# home_auto.net
KiCad netlist of a schematic drawn in EasyEDA
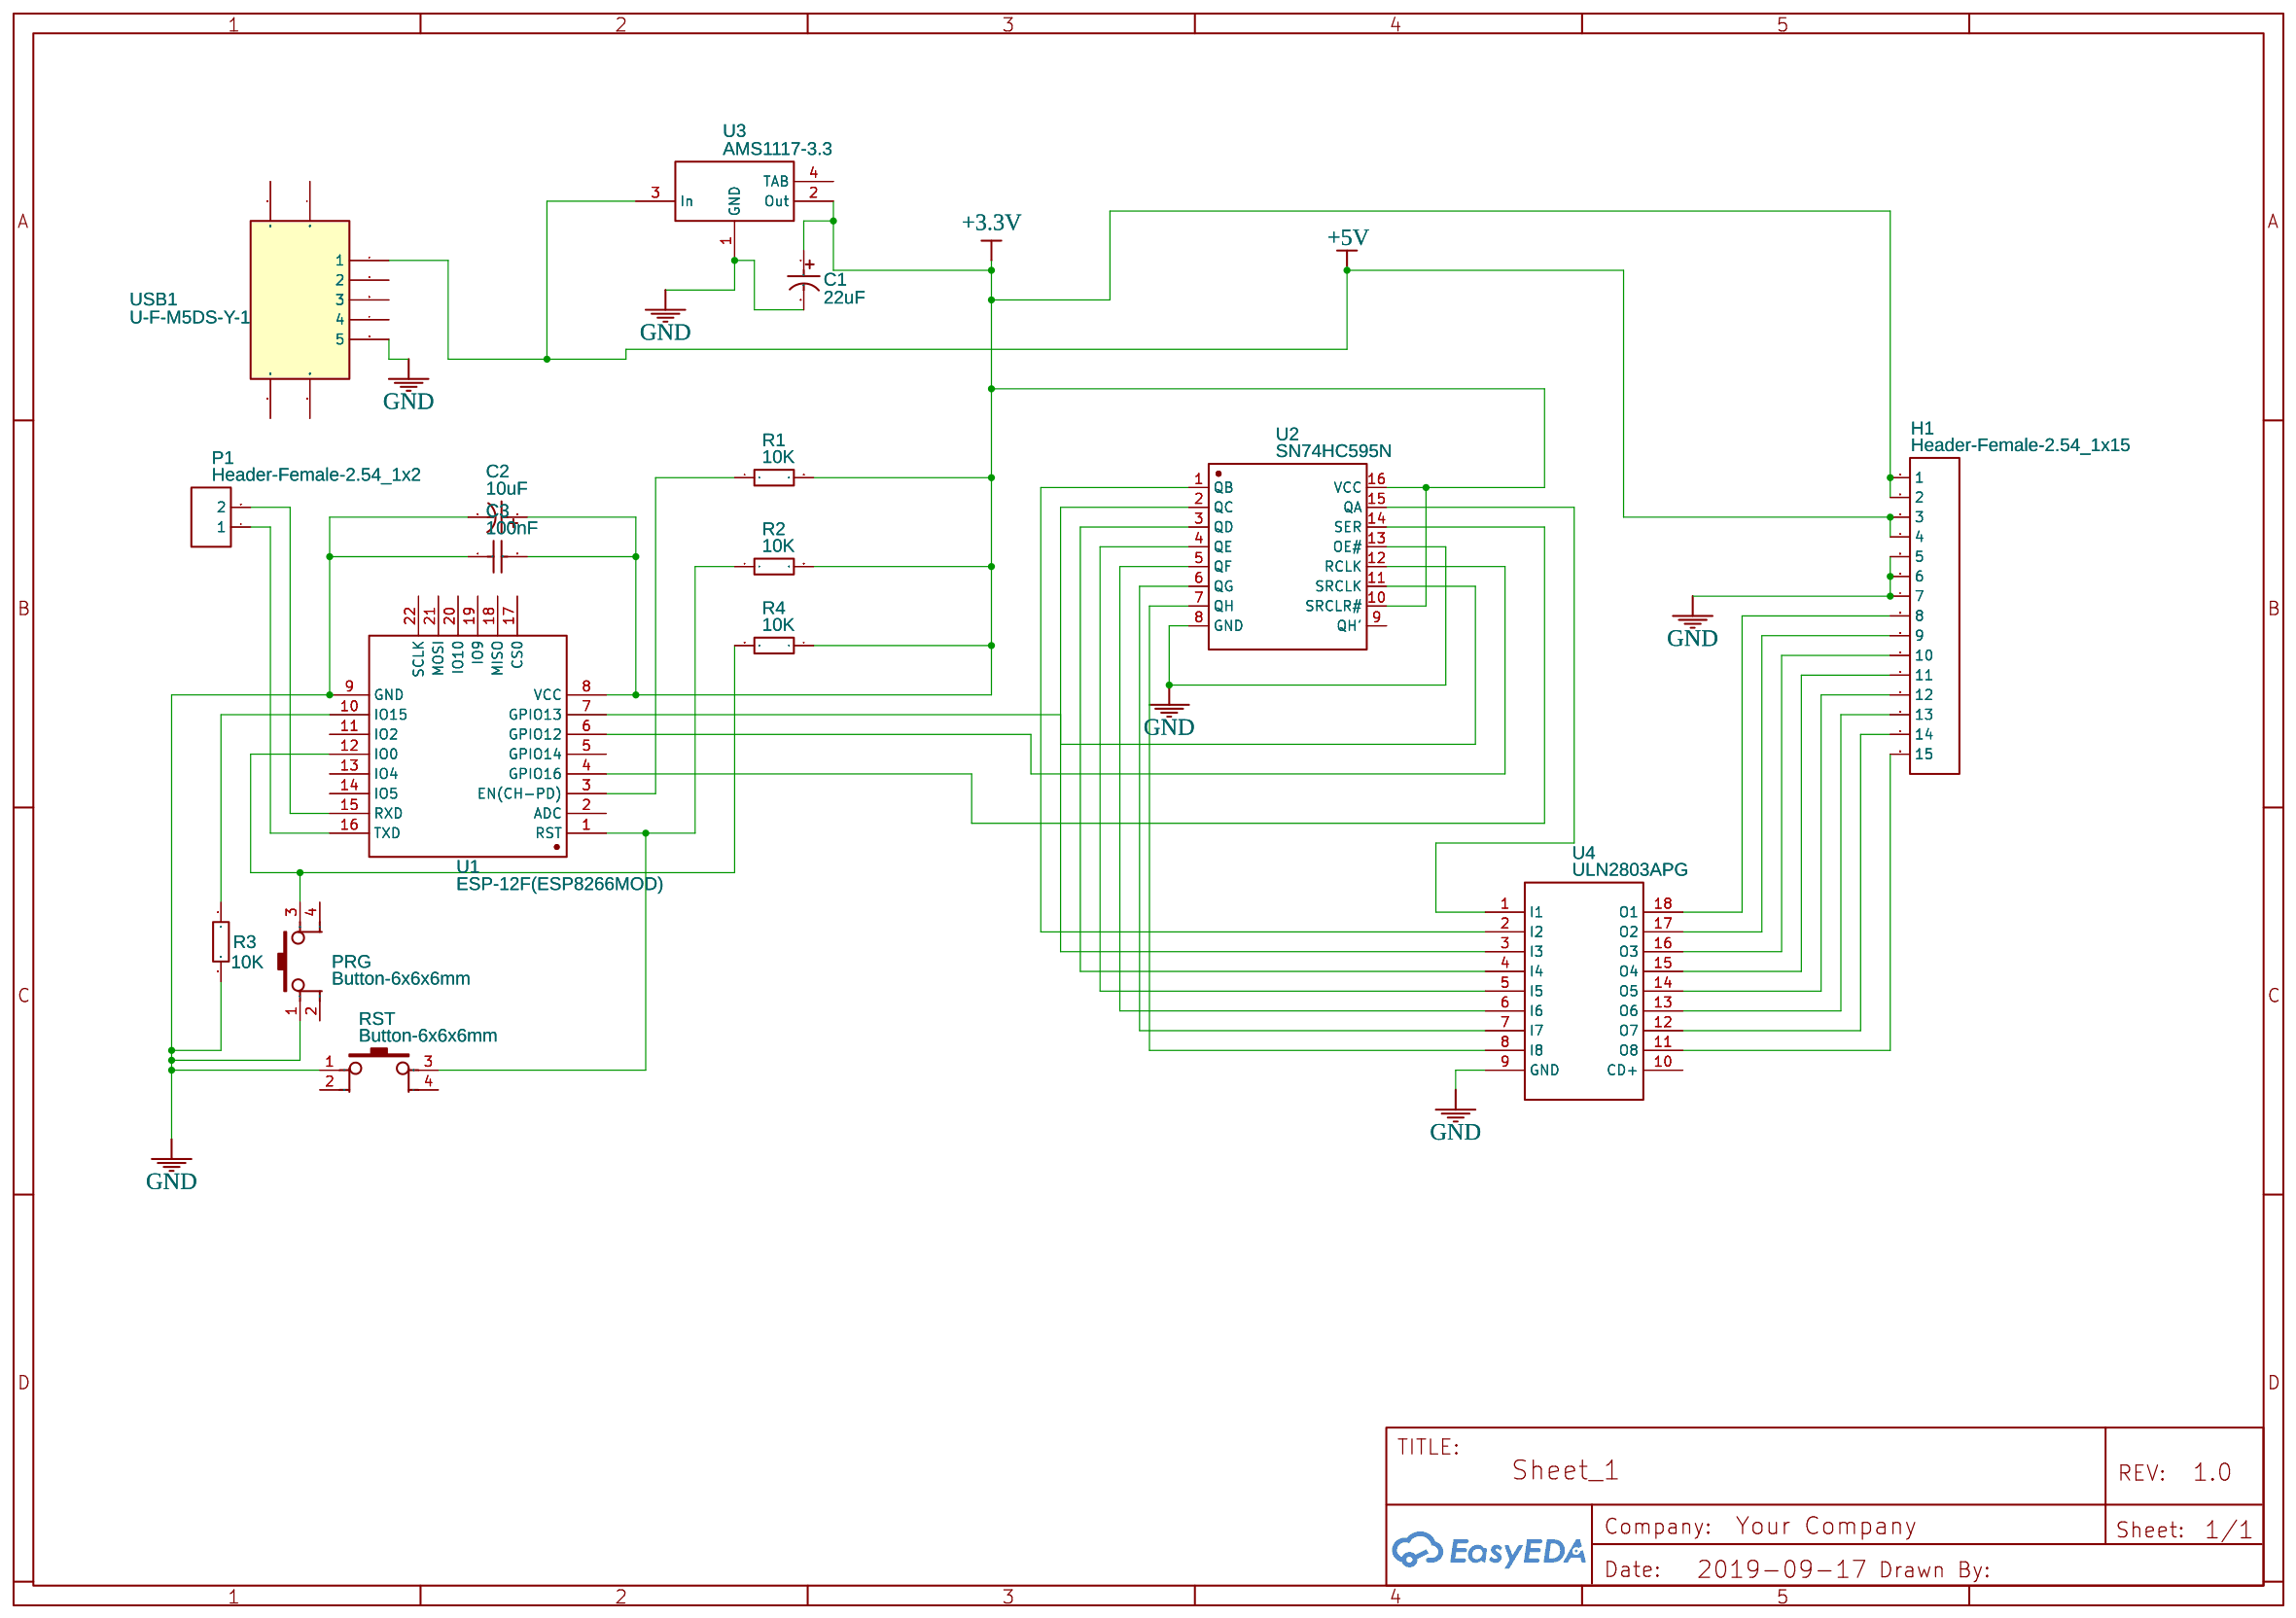
[diagram p0: schematic sheet]

(export (version "E")
  (design (tool "Eeschema 10.0.6"))
  (components
    (comp (ref "C1")
      (value "22uF")
      (fields
        (field (name "BOM_Manufacturer Part") "22uF 16V 5*11")
        (field (name "BOM_Supplier Part") "C43844")
      )
      (libsource (lib "") (part "22uF 16V 5*11"))
    )
    (comp (ref "C2")
      (value "10uF")
      (fields
        (field (name "BOM_Manufacturer Part") "10uF 16V 5*11")
        (field (name "BOM_Supplier Part") "C43799")
      )
      (libsource (lib "") (part "10uF 16V 5*11"))
    )
    (comp (ref "C3")
      (value "100nF")
      (fields
        (field (name "BOM_Manufacturer Part") "MPP104J4130510LC")
        (field (name "BOM_Supplier Part") "C109501")
      )
      (libsource (lib "") (part "MPP104J4130510LC"))
    )
    (comp (ref "H1")
      (value "Header-Female-2.54_1x15")
      (fields
        (field (name "BOM_Manufacturer Part") "220S-1*15P H=8.5MM Ytype Gold-plated")
        (field (name "BOM_Supplier Part") "C124408")
      )
      (libsource (lib "") (part "Unknown_970_310"))
    )
    (comp (ref "P1")
      (value "Header-Female-2.54_1x2")
      (fields
        (field (name "BOM_Manufacturer Part") "2.54-1*2PFemale")
        (field (name "BOM_Supplier Part") "C49661")
      )
      (libsource (lib "") (part "Unknown_105_255"))
    )
    (comp (ref "PRG")
      (value "Button-6x6x6mm")
      (fields
        (field (name "BOM_Manufacturer Part") "Switch,6*6*6Plastic head,260G, 0.25mm,Straight line")
        (field (name "BOM_Supplier Part") "C71836")
      )
      (libsource (lib "") (part "Unknown_145_480"))
    )
    (comp (ref "R1")
      (value "10K")
      (fields
        (field (name "BOM_Manufacturer Part") "MOR01SJ0103A10")
        (field (name "BOM_Supplier Part") "C64666")
      )
      (libsource (lib "") (part "MOR01SJ0103A10_1"))
    )
    (comp (ref "R2")
      (value "10K")
      (fields
        (field (name "BOM_Manufacturer Part") "MOR01SJ0103A10")
        (field (name "BOM_Supplier Part") "C64666")
      )
      (libsource (lib "") (part "MOR01SJ0103A10_1"))
    )
    (comp (ref "R3")
      (value "10K")
      (fields
        (field (name "BOM_Manufacturer Part") "MOR01SJ0103A10")
        (field (name "BOM_Supplier Part") "C64666")
      )
      (libsource (lib "") (part "MOR01SJ0103A10_2"))
    )
    (comp (ref "R4")
      (value "10K")
      (fields
        (field (name "BOM_Manufacturer Part") "MOR01SJ0103A10")
        (field (name "BOM_Supplier Part") "C64666")
      )
      (libsource (lib "") (part "MOR01SJ0103A10"))
    )
    (comp (ref "RST")
      (value "Button-6x6x6mm")
      (fields
        (field (name "BOM_Manufacturer Part") "Switch,6*6*6Plastic head,260G, 0.25mm,Straight line")
        (field (name "BOM_Supplier Part") "C71836")
      )
      (libsource (lib "") (part "Unknown_185_535"))
    )
    (comp (ref "U1")
      (value "ESP-12F(ESP8266MOD)")
      (fields (field (name "BOM_Supplier Part") "C82891"))
      (libsource (lib "") (part "Unknown_230_365"))
    )
    (comp (ref "U2")
      (value "SN74HC595N")
      (fields (field (name "BOM_Supplier Part") "C78711"))
      (libsource (lib "") (part "Unknown_645_275"))
    )
    (comp (ref "U3")
      (value "AMS1117-3.3")
      (fields (field (name "BOM_Supplier Part") "C6186"))
      (libsource (lib "") (part "Unknown_365_100"))
    )
    (comp (ref "U4")
      (value "ULN2803APG")
      (fields (field (name "BOM_Supplier Part") "C5252"))
      (libsource (lib "") (part "Unknown_795_495"))
    )
    (comp (ref "USB1")
      (value "U-F-M5DS-Y-1")
      (fields (field (name "BOM_Supplier Part") "C106818"))
      (libsource (lib "") (part "Unknown_155_145"))
    )
  )
  (nets
    (net (code "1") (name "+3.3V") (class "Default")
      (node (ref "C1") (pin "1") (pinfunction "1_1") (pintype "input"))
      (node (ref "C2") (pin "1") (pinfunction "1_1") (pintype "input"))
      (node (ref "C3") (pin "2") (pinfunction "2_2") (pintype "input"))
      (node (ref "H1") (pin "1") (pinfunction "1_1") (pintype "unspecified"))
      (node (ref "H1") (pin "2") (pinfunction "2_2") (pintype "unspecified"))
      (node (ref "R1") (pin "2") (pinfunction "2_2") (pintype "unspecified"))
      (node (ref "R2") (pin "2") (pinfunction "2_2") (pintype "unspecified"))
      (node (ref "R4") (pin "1") (pinfunction "1_1") (pintype "unspecified"))
      (node (ref "U1") (pin "8") (pinfunction "VCC_8") (pintype "unspecified"))
      (node (ref "U2") (pin "10") (pinfunction "SRCLR#_10") (pintype "unspecified"))
      (node (ref "U2") (pin "16") (pinfunction "VCC_16") (pintype "unspecified"))
      (node (ref "U3") (pin "2") (pinfunction "Out_2") (pintype "unspecified"))
    )
    (net (code "2") (name "+5V") (class "Default")
      (node (ref "H1") (pin "3") (pinfunction "3_3") (pintype "unspecified"))
      (node (ref "H1") (pin "4") (pinfunction "4_4") (pintype "unspecified"))
      (node (ref "U3") (pin "3") (pinfunction "In_3") (pintype "unspecified"))
      (node (ref "USB1") (pin "1") (pinfunction "1_1") (pintype "input"))
    )
    (net (code "3") (name "GND") (class "Default")
      (node (ref "C1") (pin "2") (pinfunction "2_2") (pintype "input"))
      (node (ref "C2") (pin "2") (pinfunction "2_2") (pintype "input"))
      (node (ref "C3") (pin "1") (pinfunction "1_1") (pintype "input"))
      (node (ref "H1") (pin "5") (pinfunction "5_5") (pintype "unspecified"))
      (node (ref "H1") (pin "6") (pinfunction "6_6") (pintype "unspecified"))
      (node (ref "H1") (pin "7") (pinfunction "7_7") (pintype "unspecified"))
      (node (ref "PRG") (pin "1") (pinfunction "1_1") (pintype "input"))
      (node (ref "R3") (pin "2") (pinfunction "2_2") (pintype "unspecified"))
      (node (ref "RST") (pin "1") (pinfunction "1_1") (pintype "input"))
      (node (ref "U1") (pin "9") (pinfunction "GND_9") (pintype "unspecified"))
      (node (ref "U2") (pin "13") (pinfunction "OE#_13") (pintype "unspecified"))
      (node (ref "U2") (pin "8") (pinfunction "GND_8") (pintype "unspecified"))
      (node (ref "U3") (pin "1") (pinfunction "GND_1") (pintype "unspecified"))
      (node (ref "U4") (pin "9") (pinfunction "GND_9") (pintype "passive"))
      (node (ref "USB1") (pin "5") (pinfunction "5_5") (pintype "input"))
    )
    (net (code "4") (name "Net-(U1-EN(CH-PD))") (class "Default")
      (node (ref "R1") (pin "1") (pinfunction "1_1") (pintype "unspecified"))
      (node (ref "U1") (pin "3") (pinfunction "EN(CH-PD)_3") (pintype "unspecified"))
    )
    (net (code "5") (name "Net-(U1-GPIO12)") (class "Default")
      (node (ref "U1") (pin "6") (pinfunction "GPIO12_6") (pintype "unspecified"))
      (node (ref "U2") (pin "12") (pinfunction "RCLK_12") (pintype "unspecified"))
    )
    (net (code "6") (name "Net-(U1-GPIO13)") (class "Default")
      (node (ref "U1") (pin "7") (pinfunction "GPIO13_7") (pintype "unspecified"))
      (node (ref "U2") (pin "11") (pinfunction "SRCLK_11") (pintype "unspecified"))
    )
    (net (code "7") (name "Net-(U1-GPIO16)") (class "Default")
      (node (ref "U1") (pin "4") (pinfunction "GPIO16_4") (pintype "unspecified"))
      (node (ref "U2") (pin "14") (pinfunction "SER_14") (pintype "unspecified"))
    )
    (net (code "8") (name "Net-(U1-IO0)") (class "Default")
      (node (ref "PRG") (pin "3") (pinfunction "3_3") (pintype "input"))
      (node (ref "R4") (pin "2") (pinfunction "2_2") (pintype "unspecified"))
      (node (ref "U1") (pin "12") (pinfunction "IO0_12") (pintype "unspecified"))
    )
    (net (code "9") (name "Net-(U1-IO15)") (class "Default")
      (node (ref "R3") (pin "1") (pinfunction "1_1") (pintype "unspecified"))
      (node (ref "U1") (pin "10") (pinfunction "IO15_10") (pintype "unspecified"))
    )
    (net (code "10") (name "Net-(U1-RST)") (class "Default")
      (node (ref "R2") (pin "1") (pinfunction "1_1") (pintype "unspecified"))
      (node (ref "RST") (pin "3") (pinfunction "3_3") (pintype "input"))
      (node (ref "U1") (pin "1") (pinfunction "RST_1") (pintype "unspecified"))
    )
    (net (code "11") (name "Net-(U1-RXD)") (class "Default")
      (node (ref "P1") (pin "2") (pinfunction "2_2") (pintype "input"))
      (node (ref "U1") (pin "15") (pinfunction "RXD_15") (pintype "unspecified"))
    )
    (net (code "12") (name "Net-(U1-TXD)") (class "Default")
      (node (ref "P1") (pin "1") (pinfunction "1_1") (pintype "input"))
      (node (ref "U1") (pin "16") (pinfunction "TXD_16") (pintype "unspecified"))
    )
    (net (code "13") (name "Net-(U2-QA)") (class "Default")
      (node (ref "U2") (pin "15") (pinfunction "QA_15") (pintype "unspecified"))
      (node (ref "U4") (pin "1") (pinfunction "I1_1") (pintype "input"))
    )
    (net (code "14") (name "Net-(U2-QB)") (class "Default")
      (node (ref "U2") (pin "1") (pinfunction "QB_1") (pintype "unspecified"))
      (node (ref "U4") (pin "2") (pinfunction "I2_2") (pintype "input"))
    )
    (net (code "15") (name "Net-(U2-QC)") (class "Default")
      (node (ref "U2") (pin "2") (pinfunction "QC_2") (pintype "unspecified"))
      (node (ref "U4") (pin "3") (pinfunction "I3_3") (pintype "input"))
    )
    (net (code "16") (name "Net-(U2-QD)") (class "Default")
      (node (ref "U2") (pin "3") (pinfunction "QD_3") (pintype "unspecified"))
      (node (ref "U4") (pin "4") (pinfunction "I4_4") (pintype "input"))
    )
    (net (code "17") (name "Net-(U2-QE)") (class "Default")
      (node (ref "U2") (pin "4") (pinfunction "QE_4") (pintype "unspecified"))
      (node (ref "U4") (pin "5") (pinfunction "I5_5") (pintype "input"))
    )
    (net (code "18") (name "Net-(U2-QF)") (class "Default")
      (node (ref "U2") (pin "5") (pinfunction "QF_5") (pintype "unspecified"))
      (node (ref "U4") (pin "6") (pinfunction "I6_6") (pintype "input"))
    )
    (net (code "19") (name "Net-(U2-QG)") (class "Default")
      (node (ref "U2") (pin "6") (pinfunction "QG_6") (pintype "unspecified"))
      (node (ref "U4") (pin "7") (pinfunction "I7_7") (pintype "input"))
    )
    (net (code "20") (name "Net-(U2-QH)") (class "Default")
      (node (ref "U2") (pin "7") (pinfunction "QH_7") (pintype "unspecified"))
      (node (ref "U4") (pin "8") (pinfunction "I8_8") (pintype "input"))
    )
    (net (code "21") (name "Net-(U4-O1)") (class "Default")
      (node (ref "H1") (pin "8") (pinfunction "8_8") (pintype "unspecified"))
      (node (ref "U4") (pin "18") (pinfunction "O1_18") (pintype "unspecified"))
    )
    (net (code "22") (name "Net-(U4-O2)") (class "Default")
      (node (ref "H1") (pin "9") (pinfunction "9_9") (pintype "unspecified"))
      (node (ref "U4") (pin "17") (pinfunction "O2_17") (pintype "unspecified"))
    )
    (net (code "23") (name "Net-(U4-O3)") (class "Default")
      (node (ref "H1") (pin "10") (pinfunction "10_10") (pintype "unspecified"))
      (node (ref "U4") (pin "16") (pinfunction "O3_16") (pintype "unspecified"))
    )
    (net (code "24") (name "Net-(U4-O4)") (class "Default")
      (node (ref "H1") (pin "11") (pinfunction "11_11") (pintype "unspecified"))
      (node (ref "U4") (pin "15") (pinfunction "O4_15") (pintype "unspecified"))
    )
    (net (code "25") (name "Net-(U4-O5)") (class "Default")
      (node (ref "H1") (pin "12") (pinfunction "12_12") (pintype "unspecified"))
      (node (ref "U4") (pin "14") (pinfunction "O5_14") (pintype "unspecified"))
    )
    (net (code "26") (name "Net-(U4-O6)") (class "Default")
      (node (ref "H1") (pin "13") (pinfunction "13_13") (pintype "unspecified"))
      (node (ref "U4") (pin "13") (pinfunction "O6_13") (pintype "unspecified"))
    )
    (net (code "27") (name "Net-(U4-O7)") (class "Default")
      (node (ref "H1") (pin "14") (pinfunction "14_14") (pintype "unspecified"))
      (node (ref "U4") (pin "12") (pinfunction "O7_12") (pintype "unspecified"))
    )
    (net (code "28") (name "Net-(U4-O8)") (class "Default")
      (node (ref "H1") (pin "15") (pinfunction "15_15") (pintype "unspecified"))
      (node (ref "U4") (pin "11") (pinfunction "O8_11") (pintype "unspecified"))
    )
    (net (code "29") (name "unconnected-(PRG-Pad2)") (class "Default")
      (node (ref "PRG") (pin "2") (pinfunction "2_2") (pintype "input"))
    )
    (net (code "30") (name "unconnected-(PRG-Pad4)") (class "Default")
      (node (ref "PRG") (pin "4") (pinfunction "4_4") (pintype "input"))
    )
    (net (code "31") (name "unconnected-(RST-Pad2)") (class "Default")
      (node (ref "RST") (pin "2") (pinfunction "2_2") (pintype "input"))
    )
    (net (code "32") (name "unconnected-(RST-Pad4)") (class "Default")
      (node (ref "RST") (pin "4") (pinfunction "4_4") (pintype "input"))
    )
    (net (code "33") (name "unconnected-(U1-ADC-Pad2)") (class "Default")
      (node (ref "U1") (pin "2") (pinfunction "ADC_2") (pintype "unspecified"))
    )
    (net (code "34") (name "unconnected-(U1-CS0-Pad17)") (class "Default")
      (node (ref "U1") (pin "17") (pinfunction "CS0_17") (pintype "unspecified"))
    )
    (net (code "35") (name "unconnected-(U1-GPIO14-Pad5)") (class "Default")
      (node (ref "U1") (pin "5") (pinfunction "GPIO14_5") (pintype "unspecified"))
    )
    (net (code "36") (name "unconnected-(U1-IO2-Pad11)") (class "Default")
      (node (ref "U1") (pin "11") (pinfunction "IO2_11") (pintype "unspecified"))
    )
    (net (code "37") (name "unconnected-(U1-IO4-Pad13)") (class "Default")
      (node (ref "U1") (pin "13") (pinfunction "IO4_13") (pintype "unspecified"))
    )
    (net (code "38") (name "unconnected-(U1-IO5-Pad14)") (class "Default")
      (node (ref "U1") (pin "14") (pinfunction "IO5_14") (pintype "unspecified"))
    )
    (net (code "39") (name "unconnected-(U1-IO9-Pad19)") (class "Default")
      (node (ref "U1") (pin "19") (pinfunction "IO9_19") (pintype "unspecified"))
    )
    (net (code "40") (name "unconnected-(U1-IO10-Pad20)") (class "Default")
      (node (ref "U1") (pin "20") (pinfunction "IO10_20") (pintype "unspecified"))
    )
    (net (code "41") (name "unconnected-(U1-MISO-Pad18)") (class "Default")
      (node (ref "U1") (pin "18") (pinfunction "MISO_18") (pintype "unspecified"))
    )
    (net (code "42") (name "unconnected-(U1-MOSI-Pad21)") (class "Default")
      (node (ref "U1") (pin "21") (pinfunction "MOSI_21") (pintype "unspecified"))
    )
    (net (code "43") (name "unconnected-(U1-SCLK-Pad22)") (class "Default")
      (node (ref "U1") (pin "22") (pinfunction "SCLK_22") (pintype "unspecified"))
    )
    (net (code "44") (name "unconnected-(U2-QH'-Pad9)") (class "Default")
      (node (ref "U2") (pin "9") (pinfunction "QH'_9") (pintype "unspecified"))
    )
    (net (code "45") (name "unconnected-(U3-TAB-Pad4)") (class "Default")
      (node (ref "U3") (pin "4") (pinfunction "TAB_4") (pintype "unspecified"))
    )
    (net (code "46") (name "unconnected-(U4-CD+-Pad10)") (class "Default")
      (node (ref "U4") (pin "10") (pinfunction "CD+_10") (pintype "unspecified"))
    )
    (net (code "47") (name "unconnected-(USB1-MTN1-Pad0)") (class "Default")
      (node (ref "USB1") (pin "0") (pinfunction "MTN1_0") (pintype "input"))
    )
    (net (code "48") (name "unconnected-(USB1-MTN3-Pad7)") (class "Default")
      (node (ref "USB1") (pin "7") (pinfunction "MTN3_7") (pintype "input"))
    )
    (net (code "49") (name "unconnected-(USB1-MTN4-Pad0)") (class "Default")
      (node (ref "USB1") (pin "0") (pinfunction "MTN4_0") (pintype "input"))
    )
    (net (code "50") (name "unconnected-(USB1-MTN6-Pad6)") (class "Default")
      (node (ref "USB1") (pin "6") (pinfunction "MTN6_6") (pintype "input"))
    )
    (net (code "51") (name "unconnected-(USB1-Pad2)") (class "Default")
      (node (ref "USB1") (pin "2") (pinfunction "2_2") (pintype "input"))
    )
    (net (code "52") (name "unconnected-(USB1-Pad3)") (class "Default")
      (node (ref "USB1") (pin "3") (pinfunction "3_3") (pintype "input"))
    )
    (net (code "53") (name "unconnected-(USB1-Pad4)") (class "Default")
      (node (ref "USB1") (pin "4") (pinfunction "4_4") (pintype "input"))
    )
  )
)
